# Sheet1.net
KiCad netlist of a schematic drawn in Altium Designer
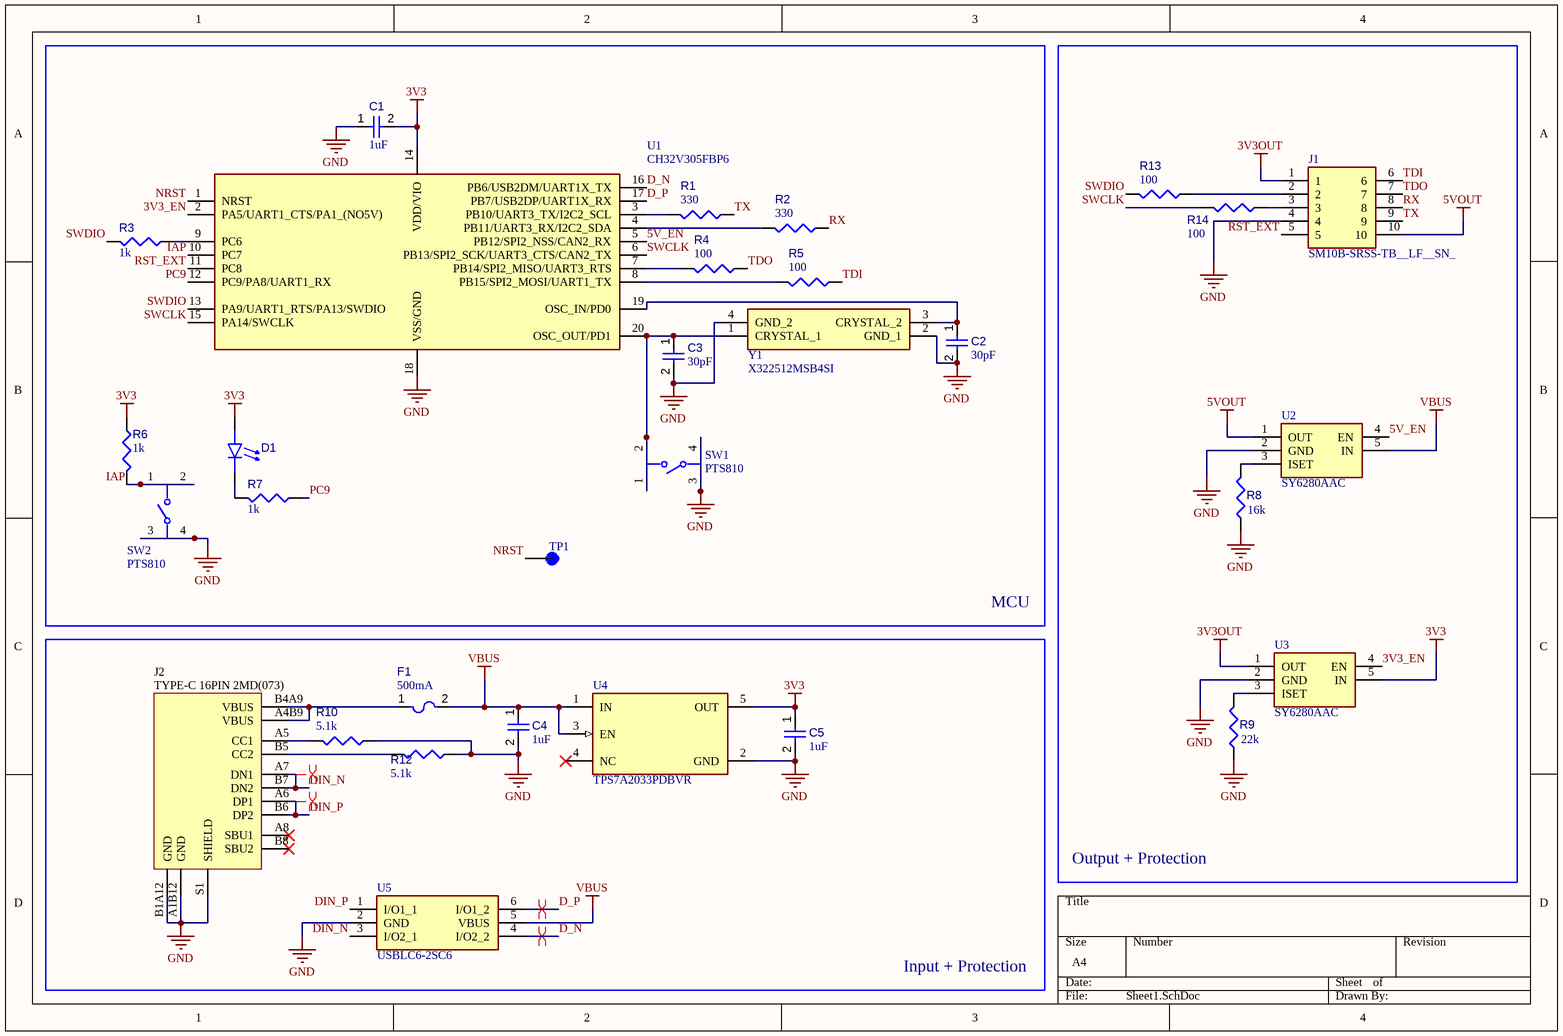
[diagram p0: Sheet1.SchDoc]

(export (version "E")
  (design (tool "Eeschema 10.0.6"))
  (components
    (comp (ref "C1")
      (value "1uF")
      (footprint "CAP 0603_1608")
      (description "Capacitor")
      (fields (field (name "Comment") "Capacitors,C126631,1uF"))
      (libsource (lib "Western Formula Racing") (part "CAP-NP-2"))
    )
    (comp (ref "C2")
      (value "30pF")
      (footprint "CAP 0402_1005")
      (description "Capacitor")
      (fields (field (name "Comment") "Capacitors,C526980,30pF"))
      (libsource (lib "Western Formula Racing") (part "CAP-NP-2"))
    )
    (comp (ref "C3")
      (value "30pF")
      (footprint "CAP 0402_1005")
      (description "Capacitor")
      (fields (field (name "Comment") "Capacitors,C526980,30pF"))
      (libsource (lib "Western Formula Racing") (part "CAP-NP-2"))
    )
    (comp (ref "C4")
      (value "1uF")
      (footprint "CAP 0603_1608")
      (description "Capacitor")
      (fields (field (name "Comment") "Capacitors,C126631,1uF"))
      (libsource (lib "Western Formula Racing") (part "CAP-NP-2"))
    )
    (comp (ref "C5")
      (value "1uF")
      (footprint "CAP 0603_1608")
      (description "Capacitor")
      (fields (field (name "Comment") "Capacitors,C126631,1uF"))
      (libsource (lib "Western Formula Racing") (part "CAP-NP-2"))
    )
    (comp (ref "D1")
      (value "KT-0805G")
      (footprint "KT-0805G")
      (libsource (lib "Western Formula Racing") (part "DIODE-LED-2"))
    )
    (comp (ref "F1")
      (value "Fuses,500mA,C7472536")
      (footprint "LFUS-467_V")
      (description "Fuse")
      (fields (field (name "CURRENT RATING") "500mA"))
      (libsource (lib "Western Formula Racing") (part "FUSE-2"))
    )
    (comp (ref "J1")
      (value "SM10B-SRSS-TB__LF__SN_")
      (footprint "custom:SM10B-SRSS-TB")
      (description "Connector")
      (fields (field (name "MANUFACTURER_PART_NUMBER") "SM10B-SRSS-TB (LF)(SN)"))
      (libsource (lib "custom") (part "SM10B-SRSS-TB__LF__SN_"))
    )
    (comp (ref "J2")
      (value "TYPE-C 16PIN 2MD(073)")
      (footprint "custom:USB-C-SMD_TYPE-C-16PIN-2MD-073")
      (description "USB-C (USB TYPE-C) Receptacle Connector 16 Position Surface Mount, Right Angle")
      (libsource (lib "custom") (part "TYPE-C_16PIN_2MD_073"))
    )
    (comp (ref "R1")
      (value "330")
      (footprint "RESC0402(1005)_L")
      (description "Resistor")
      (fields (field (name "Comment") "Resistors,C25104,330"))
      (libsource (lib "Western Formula Racing") (part "RES-2"))
    )
    (comp (ref "R2")
      (value "330")
      (footprint "RESC0402(1005)_L")
      (description "Resistor")
      (fields (field (name "Comment") "Resistors,C25104,330"))
      (libsource (lib "Western Formula Racing") (part "RES-2"))
    )
    (comp (ref "R3")
      (value "1k")
      (footprint "RESC0402(1005)_L")
      (description "Resistor")
      (fields (field (name "Comment") "Resistors,C11702,1k"))
      (libsource (lib "Western Formula Racing") (part "RES-2"))
    )
    (comp (ref "R4")
      (value "100")
      (footprint "RESC0402(1005)_L")
      (description "Resistor")
      (fields (field (name "Comment") "Resistors,C25076,100"))
      (libsource (lib "Western Formula Racing") (part "RES-2"))
    )
    (comp (ref "R5")
      (value "100")
      (footprint "RESC0402(1005)_L")
      (description "Resistor")
      (fields (field (name "Comment") "Resistors,C25076,100"))
      (libsource (lib "Western Formula Racing") (part "RES-2"))
    )
    (comp (ref "R6")
      (value "1k")
      (footprint "RESC0402(1005)_L")
      (description "Resistor")
      (fields (field (name "Comment") "Resistors,C11702,1k"))
      (libsource (lib "Western Formula Racing") (part "RES-2"))
    )
    (comp (ref "R7")
      (value "1k")
      (footprint "RESC0402(1005)_L")
      (description "Resistor")
      (fields (field (name "Comment") "Resistors,C11702,1k"))
      (libsource (lib "Western Formula Racing") (part "RES-2"))
    )
    (comp (ref "R8")
      (value "16k")
      (footprint "RESC0402(1005)_L")
      (description "Resistor")
      (fields (field (name "Comment") "Resistors,C25759,16k"))
      (libsource (lib "Western Formula Racing") (part "RES-2"))
    )
    (comp (ref "R9")
      (value "22k")
      (footprint "RESC0402(1005)_L")
      (description "Resistor")
      (fields (field (name "Comment") "Resistors,C25768,22k"))
      (libsource (lib "Western Formula Racing") (part "RES-2"))
    )
    (comp (ref "R10")
      (value "5.1k")
      (footprint "RESC0402(1005)_L")
      (description "Resistor")
      (fields (field (name "Comment") "Resistors,C25905,5.1k"))
      (libsource (lib "Western Formula Racing") (part "RES-2"))
    )
    (comp (ref "R12")
      (value "5.1k")
      (footprint "RESC0402(1005)_L")
      (description "Resistor")
      (fields (field (name "Comment") "Resistors,C25905,5.1k"))
      (libsource (lib "Western Formula Racing") (part "RES-2"))
    )
    (comp (ref "R13")
      (value "100")
      (footprint "RESC0402(1005)_L")
      (description "Resistor")
      (fields (field (name "Comment") "Resistors,C25076,100"))
      (libsource (lib "Western Formula Racing") (part "RES-2"))
    )
    (comp (ref "R14")
      (value "100")
      (footprint "RESC0402(1005)_L")
      (description "Resistor")
      (fields (field (name "Comment") "Resistors,C25076,100"))
      (libsource (lib "Western Formula Racing") (part "RES-2"))
    )
    (comp (ref "SW1")
      (value "PTS810")
      (footprint "FP-PTS810_SJG_250_SMTR_LF-MFG")
      (description "SWITCH TACTILE SPST-NO 0.05A 16V")
      (fields
        (field (name "MANUFACTURER") "C&K Components")
        (field (name "OCTOPART") "https://octopart.com/pts810sjg250smtrlfs-c%26k+components-29380277")
      )
      (libsource (lib "custom") (part "CMP-10040-000011-1"))
    )
    (comp (ref "SW2")
      (value "PTS810")
      (footprint "FP-PTS810_SJG_250_SMTR_LF-MFG")
      (description "SWITCH TACTILE SPST-NO 0.05A 16V")
      (fields
        (field (name "MANUFACTURER") "C&K Components")
        (field (name "OCTOPART") "https://octopart.com/pts810sjg250smtrlfs-c%26k+components-29380277")
      )
      (libsource (lib "custom") (part "CMP-10040-000011-1"))
    )
    (comp (ref "TP1")
      (value "5000")
      (footprint "KEYSTONE_5000")
      (description "Test Point Miniature THM H .300 Nylon 46 Insulated Red PhosBronze/Silver")
      (fields (field (name "MF") "Keystone Electronics"))
      (libsource (lib "Western Formula Racing") (part "5000"))
    )
    (comp (ref "U1")
      (value "CH32V305FBP6")
      (footprint "custom:SOP65P640X110-20N")
      (description "Integrated Circuit")
      (libsource (lib "custom") (part "CH32V305FBP6"))
    )
    (comp (ref "U2")
      (value "SY6280AAC")
      (footprint "custom:SOT95P285X140-5N")
      (description "Integrated Circuit")
      (fields
        (field (name "MANUFACTURER_PART_NUMBER") "SMD IC SY6280AAC")
        (field (name "MOUSER PART NUMBER") "909-SMDICSY6280AAC")
      )
      (libsource (lib "custom") (part "SY6280AAC"))
    )
    (comp (ref "U3")
      (value "SY6280AAC")
      (footprint "custom:SOT95P285X140-5N")
      (description "Integrated Circuit")
      (fields
        (field (name "MANUFACTURER_PART_NUMBER") "SMD IC SY6280AAC")
        (field (name "MOUSER PART NUMBER") "909-SMDICSY6280AAC")
      )
      (libsource (lib "custom") (part "SY6280AAC"))
    )
    (comp (ref "U4")
      (value "TPS7A2033PDBVR")
      (footprint "FP-DBV0005A-IPC_B")
      (description "IC REG LINEAR 3.3V 300MA SOT23-5")
      (libsource (lib "custom") (part "TPS7A2033PDBVR"))
    )
    (comp (ref "U5")
      (value "USBLC6-2SC6")
      (footprint "custom:SOT95P280X145-6N")
      (description "Integrated Circuit")
      (fields (field (name "MOUSER PART NUMBER") "511-USBLC6-2SC6"))
      (libsource (lib "custom") (part "USBLC6-2SC6"))
    )
    (comp (ref "Y1")
      (value "X322512MSB4SI")
      (footprint "custom:X322512MSB4SI")
      (description "Crystal or Oscillator")
      (libsource (lib "custom") (part "X322512MSB4SI"))
    )
  )
  (nets
    (net (code "1") (name "/3V3_EN") (class "Default")
      (node (ref "U1") (pin "2") (pinfunction "PA5/UART1_CTS/PA1_(NO5V)_2") (pintype "passive"))
      (node (ref "U3") (pin "4") (pinfunction "EN_4") (pintype "passive"))
    )
    (net (code "2") (name "/5V_EN") (class "Default")
      (node (ref "U1") (pin "5") (pinfunction "PB12/SPI2_NSS/CAN2_RX_5") (pintype "passive"))
      (node (ref "U2") (pin "4") (pinfunction "EN_4") (pintype "passive"))
    )
    (net (code "3") (name "/DIN_N") (class "Default")
      (node (ref "J2") (pin "A7") (pinfunction "DN1_A7") (pintype "passive"))
      (node (ref "J2") (pin "B7") (pinfunction "DN2_B7") (pintype "passive"))
      (node (ref "U5") (pin "3") (pinfunction "I/O2_1_3") (pintype "passive"))
    )
    (net (code "4") (name "/DIN_P") (class "Default")
      (node (ref "J2") (pin "A6") (pinfunction "DP1_A6") (pintype "passive"))
      (node (ref "J2") (pin "B6") (pinfunction "DP2_B6") (pintype "passive"))
      (node (ref "U5") (pin "1") (pinfunction "I/O1_1_1") (pintype "passive"))
    )
    (net (code "5") (name "/D_N") (class "Default")
      (node (ref "U1") (pin "16") (pinfunction "PB6/USB2DM/UART1X_TX_16") (pintype "passive"))
      (node (ref "U5") (pin "4") (pinfunction "I/O2_2_4") (pintype "passive"))
    )
    (net (code "6") (name "/D_P") (class "Default")
      (node (ref "U1") (pin "17") (pinfunction "PB7/USB2DP/UART1X_RX_17") (pintype "passive"))
      (node (ref "U5") (pin "6") (pinfunction "I/O1_2_6") (pintype "passive"))
    )
    (net (code "7") (name "/IAP") (class "Default")
      (node (ref "R6") (pin "2") (pinfunction "2_2") (pintype "passive"))
      (node (ref "SW2") (pin "1") (pinfunction "1_1") (pintype "passive"))
      (node (ref "SW2") (pin "2") (pinfunction "2_2") (pintype "passive"))
      (node (ref "U1") (pin "10") (pinfunction "PC7_10") (pintype "passive"))
    )
    (net (code "8") (name "/NRST") (class "Default")
      (node (ref "TP1") (pin "TP") (pinfunction "TP_TP") (pintype "passive"))
      (node (ref "U1") (pin "1") (pinfunction "NRST_1") (pintype "passive"))
    )
    (net (code "9") (name "/PC9") (class "Default")
      (node (ref "R7") (pin "1") (pinfunction "1_1") (pintype "passive"))
      (node (ref "U1") (pin "12") (pinfunction "PC9/PA8/UART1_RX_12") (pintype "passive"))
    )
    (net (code "10") (name "/RST_EXT") (class "Default")
      (node (ref "J1") (pin "5") (pinfunction "5_5") (pintype "passive"))
      (node (ref "U1") (pin "11") (pinfunction "PC8_11") (pintype "passive"))
    )
    (net (code "11") (name "/RX") (class "Default")
      (node (ref "J1") (pin "8") (pinfunction "8_8") (pintype "passive"))
      (node (ref "R2") (pin "1") (pinfunction "1_1") (pintype "passive"))
    )
    (net (code "12") (name "/SWCLK") (class "Default")
      (node (ref "R14") (pin "2") (pinfunction "2_2") (pintype "passive"))
      (node (ref "U1") (pin "15") (pinfunction "PA14/SWCLK_15") (pintype "passive"))
      (node (ref "U1") (pin "6") (pinfunction "PB13/SPI2_SCK/UART3_CTS/CAN2_TX_6") (pintype "passive"))
    )
    (net (code "13") (name "/SWDIO") (class "Default")
      (node (ref "R13") (pin "2") (pinfunction "2_2") (pintype "passive"))
      (node (ref "R3") (pin "2") (pinfunction "2_2") (pintype "passive"))
      (node (ref "U1") (pin "13") (pinfunction "PA9/UART1_RTS/PA13/SWDIO_13") (pintype "passive"))
    )
    (net (code "14") (name "/TDI") (class "Default")
      (node (ref "J1") (pin "6") (pinfunction "6_6") (pintype "passive"))
      (node (ref "R5") (pin "1") (pinfunction "1_1") (pintype "passive"))
    )
    (net (code "15") (name "/TDO") (class "Default")
      (node (ref "J1") (pin "7") (pinfunction "7_7") (pintype "passive"))
      (node (ref "R4") (pin "1") (pinfunction "1_1") (pintype "passive"))
    )
    (net (code "16") (name "/TX") (class "Default")
      (node (ref "J1") (pin "9") (pinfunction "9_9") (pintype "passive"))
      (node (ref "R1") (pin "1") (pinfunction "1_1") (pintype "passive"))
    )
    (net (code "17") (name "3V3") (class "Default")
      (node (ref "C1") (pin "2") (pinfunction "2_2") (pintype "passive"))
      (node (ref "C5") (pin "1") (pinfunction "1_1") (pintype "passive"))
      (node (ref "D1") (pin "2") (pinfunction "A_2") (pintype "passive"))
      (node (ref "R6") (pin "1") (pinfunction "1_1") (pintype "passive"))
      (node (ref "U1") (pin "14") (pinfunction "VDD/VIO_14") (pintype "passive"))
      (node (ref "U3") (pin "5") (pinfunction "IN_5") (pintype "passive"))
      (node (ref "U4") (pin "5") (pinfunction "OUT_5") (pintype "passive"))
    )
    (net (code "18") (name "3V3OUT") (class "Default")
      (node (ref "J1") (pin "1") (pinfunction "1_1") (pintype "passive"))
      (node (ref "U3") (pin "1") (pinfunction "OUT_1") (pintype "passive"))
    )
    (net (code "19") (name "5VOUT") (class "Default")
      (node (ref "J1") (pin "10") (pinfunction "10_10") (pintype "passive"))
      (node (ref "U2") (pin "1") (pinfunction "OUT_1") (pintype "passive"))
    )
    (net (code "20") (name "GND") (class "Default")
      (node (ref "C1") (pin "1") (pinfunction "1_1") (pintype "passive"))
      (node (ref "C2") (pin "2") (pinfunction "2_2") (pintype "passive"))
      (node (ref "C3") (pin "2") (pinfunction "2_2") (pintype "passive"))
      (node (ref "C4") (pin "2") (pinfunction "2_2") (pintype "passive"))
      (node (ref "C5") (pin "2") (pinfunction "2_2") (pintype "passive"))
      (node (ref "J1") (pin "4") (pinfunction "4_4") (pintype "passive"))
      (node (ref "J2") (pin "A1B12") (pinfunction "GND_A1B12") (pintype "passive"))
      (node (ref "J2") (pin "B1A12") (pinfunction "GND_B1A12") (pintype "passive"))
      (node (ref "J2") (pin "S1") (pinfunction "SHIELD_S1") (pintype "passive"))
      (node (ref "R10") (pin "1") (pinfunction "1_1") (pintype "passive"))
      (node (ref "R12") (pin "1") (pinfunction "1_1") (pintype "passive"))
      (node (ref "R8") (pin "1") (pinfunction "1_1") (pintype "passive"))
      (node (ref "R9") (pin "1") (pinfunction "1_1") (pintype "passive"))
      (node (ref "SW1") (pin "3") (pinfunction "3_3") (pintype "passive"))
      (node (ref "SW1") (pin "4") (pinfunction "4_4") (pintype "passive"))
      (node (ref "SW2") (pin "3") (pinfunction "3_3") (pintype "passive"))
      (node (ref "SW2") (pin "4") (pinfunction "4_4") (pintype "passive"))
      (node (ref "U1") (pin "18") (pinfunction "VSS/GND_18") (pintype "passive"))
      (node (ref "U2") (pin "2") (pinfunction "GND_2") (pintype "passive"))
      (node (ref "U3") (pin "2") (pinfunction "GND_2") (pintype "passive"))
      (node (ref "U4") (pin "2") (pinfunction "GND_2") (pintype "power_in"))
      (node (ref "U5") (pin "2") (pinfunction "GND_2") (pintype "passive"))
      (node (ref "Y1") (pin "2") (pinfunction "GND_1_2") (pintype "passive"))
      (node (ref "Y1") (pin "4") (pinfunction "GND_2_4") (pintype "passive"))
    )
    (net (code "21") (name "Net-(D1-K)") (class "Default")
      (node (ref "D1") (pin "1") (pinfunction "K_1") (pintype "passive"))
      (node (ref "R7") (pin "2") (pinfunction "2_2") (pintype "passive"))
    )
    (net (code "22") (name "Net-(F1-Pad1)") (class "Default")
      (node (ref "F1") (pin "1") (pinfunction "1_1") (pintype "passive"))
      (node (ref "J2") (pin "A4B9") (pinfunction "VBUS_A4B9") (pintype "passive"))
      (node (ref "J2") (pin "B4A9") (pinfunction "VBUS_B4A9") (pintype "passive"))
    )
    (net (code "23") (name "Net-(J1-Pad2)") (class "Default")
      (node (ref "J1") (pin "2") (pinfunction "2_2") (pintype "passive"))
      (node (ref "R13") (pin "1") (pinfunction "1_1") (pintype "passive"))
    )
    (net (code "24") (name "Net-(J1-Pad3)") (class "Default")
      (node (ref "J1") (pin "3") (pinfunction "3_3") (pintype "passive"))
      (node (ref "R14") (pin "1") (pinfunction "1_1") (pintype "passive"))
    )
    (net (code "25") (name "Net-(J2-CC1)") (class "Default")
      (node (ref "J2") (pin "A5") (pinfunction "CC1_A5") (pintype "passive"))
      (node (ref "R10") (pin "2") (pinfunction "2_2") (pintype "passive"))
    )
    (net (code "26") (name "Net-(J2-CC2)") (class "Default")
      (node (ref "J2") (pin "B5") (pinfunction "CC2_B5") (pintype "passive"))
      (node (ref "R12") (pin "2") (pinfunction "2_2") (pintype "passive"))
    )
    (net (code "27") (name "Net-(U1-OSC_IN{slash}PD0)") (class "Default")
      (node (ref "C2") (pin "1") (pinfunction "1_1") (pintype "passive"))
      (node (ref "U1") (pin "19") (pinfunction "OSC_IN/PD0_19") (pintype "passive"))
      (node (ref "Y1") (pin "3") (pinfunction "CRYSTAL_2_3") (pintype "passive"))
    )
    (net (code "28") (name "Net-(U1-OSC_OUT{slash}PD1)") (class "Default")
      (node (ref "C3") (pin "1") (pinfunction "1_1") (pintype "passive"))
      (node (ref "SW1") (pin "1") (pinfunction "1_1") (pintype "passive"))
      (node (ref "SW1") (pin "2") (pinfunction "2_2") (pintype "passive"))
      (node (ref "U1") (pin "20") (pinfunction "OSC_OUT/PD1_20") (pintype "passive"))
      (node (ref "Y1") (pin "1") (pinfunction "CRYSTAL_1_1") (pintype "passive"))
    )
    (net (code "29") (name "Net-(U1-PB10{slash}UART3_TX{slash}I2C2_SCL)") (class "Default")
      (node (ref "R1") (pin "2") (pinfunction "2_2") (pintype "passive"))
      (node (ref "U1") (pin "3") (pinfunction "PB10/UART3_TX/I2C2_SCL_3") (pintype "passive"))
    )
    (net (code "30") (name "Net-(U1-PB11{slash}UART3_RX{slash}I2C2_SDA)") (class "Default")
      (node (ref "R2") (pin "2") (pinfunction "2_2") (pintype "passive"))
      (node (ref "U1") (pin "4") (pinfunction "PB11/UART3_RX/I2C2_SDA_4") (pintype "passive"))
    )
    (net (code "31") (name "Net-(U1-PB14{slash}SPI2_MISO{slash}UART3_RTS)") (class "Default")
      (node (ref "R4") (pin "2") (pinfunction "2_2") (pintype "passive"))
      (node (ref "U1") (pin "7") (pinfunction "PB14/SPI2_MISO/UART3_RTS_7") (pintype "passive"))
    )
    (net (code "32") (name "Net-(U1-PB15{slash}SPI2_MOSI{slash}UART1_TX)") (class "Default")
      (node (ref "R5") (pin "2") (pinfunction "2_2") (pintype "passive"))
      (node (ref "U1") (pin "8") (pinfunction "PB15/SPI2_MOSI/UART1_TX_8") (pintype "passive"))
    )
    (net (code "33") (name "Net-(U1-PC6)") (class "Default")
      (node (ref "R3") (pin "1") (pinfunction "1_1") (pintype "passive"))
      (node (ref "U1") (pin "9") (pinfunction "PC6_9") (pintype "passive"))
    )
    (net (code "34") (name "Net-(U2-ISET)") (class "Default")
      (node (ref "R8") (pin "2") (pinfunction "2_2") (pintype "passive"))
      (node (ref "U2") (pin "3") (pinfunction "ISET_3") (pintype "passive"))
    )
    (net (code "35") (name "Net-(U3-ISET)") (class "Default")
      (node (ref "R9") (pin "2") (pinfunction "2_2") (pintype "passive"))
      (node (ref "U3") (pin "3") (pinfunction "ISET_3") (pintype "passive"))
    )
    (net (code "36") (name "VBUS") (class "Default")
      (node (ref "C4") (pin "1") (pinfunction "1_1") (pintype "passive"))
      (node (ref "F1") (pin "2") (pinfunction "2_2") (pintype "passive"))
      (node (ref "U2") (pin "5") (pinfunction "IN_5") (pintype "passive"))
      (node (ref "U4") (pin "1") (pinfunction "IN_1") (pintype "power_in"))
      (node (ref "U4") (pin "3") (pinfunction "EN_3") (pintype "input"))
      (node (ref "U5") (pin "5") (pinfunction "VBUS_5") (pintype "passive"))
    )
    (net (code "37") (name "unconnected-(J2-SBU1-PadA8)") (class "Default")
      (node (ref "J2") (pin "A8") (pinfunction "SBU1_A8") (pintype "passive+no_connect"))
    )
    (net (code "38") (name "unconnected-(J2-SBU2-PadB8)") (class "Default")
      (node (ref "J2") (pin "B8") (pinfunction "SBU2_B8") (pintype "passive+no_connect"))
    )
    (net (code "39") (name "unconnected-(U4-NC-Pad4)") (class "Default")
      (node (ref "U4") (pin "4") (pinfunction "NC_4") (pintype "passive+no_connect"))
    )
  )
)
